# rgb_v2_0.net
KiCad netlist of a schematic drawn in EAGLE
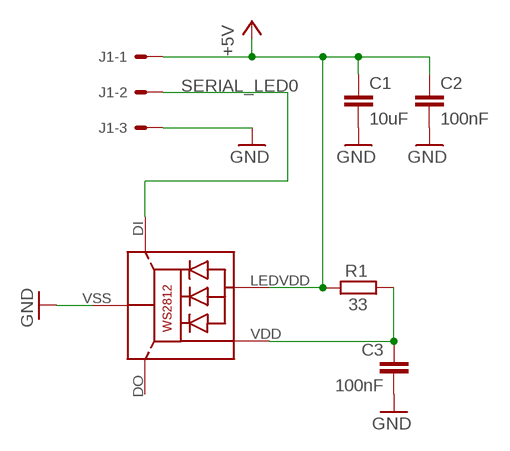
[diagram p0: schematic, sheet 1]

(export (version "E")
  (design (tool "Eeschema 10.0.6"))
  (components
    (comp (ref "C1")
      (value "10uF")
      (footprint "eagle-import:C0603")
      (libsource (lib "eagle-import") (part "C-EUC0603"))
    )
    (comp (ref "C2")
      (value "100nF")
      (footprint "eagle-import:C0402")
      (libsource (lib "eagle-import") (part "C-EUC0402"))
    )
    (comp (ref "C3")
      (value "100nF")
      (footprint "eagle-import:C0402")
      (libsource (lib "eagle-import") (part "C-EUC0402"))
    )
    (comp (ref "J1")
      (value "22-05-7038-03")
      (footprint "eagle-import:7395-03")
      (libsource (lib "eagle-import") (part "22-?-0305-7038"))
    )
    (comp (ref "LED1")
      (value "WS2812LARGER")
      (footprint "eagle-import:WS2812_LARGER")
      (libsource (lib "eagle-import") (part "WS2812LARGER"))
    )
    (comp (ref "R1")
      (value "33")
      (footprint "eagle-import:R0402")
      (libsource (lib "eagle-import") (part "R-EU_R0402"))
    )
  )
  (nets
    (net (code "1") (name "+5V") (class "Default")
      (node (ref "C1") (pin "1") (pinfunction "1_1") (pintype "passive"))
      (node (ref "C2") (pin "1") (pinfunction "1_1") (pintype "passive"))
      (node (ref "J1") (pin "1") (pinfunction "S_1") (pintype "passive"))
      (node (ref "LED1") (pin "LEDVDD") (pinfunction "LEDVDD_LEDVDD") (pintype "power_in"))
      (node (ref "R1") (pin "2") (pinfunction "2_2") (pintype "passive"))
    )
    (net (code "2") (name "/SERIAL_LED0") (class "Default")
      (node (ref "J1") (pin "2") (pinfunction "S_2") (pintype "passive"))
      (node (ref "LED1") (pin "DI") (pinfunction "DI_DI") (pintype "input"))
    )
    (net (code "3") (name "GND") (class "Default")
      (node (ref "C1") (pin "2") (pinfunction "2_2") (pintype "passive"))
      (node (ref "C2") (pin "2") (pinfunction "2_2") (pintype "passive"))
      (node (ref "C3") (pin "2") (pinfunction "2_2") (pintype "passive"))
      (node (ref "J1") (pin "3") (pinfunction "S_3") (pintype "passive"))
      (node (ref "LED1") (pin "VSS") (pinfunction "GND_VSS") (pintype "power_in"))
    )
    (net (code "4") (name "Net-(C3-Pad1)") (class "Default")
      (node (ref "C3") (pin "1") (pinfunction "1_1") (pintype "passive"))
      (node (ref "LED1") (pin "VDD") (pinfunction "VDD_VDD") (pintype "power_in"))
      (node (ref "R1") (pin "1") (pinfunction "1_1") (pintype "passive"))
    )
    (net (code "5") (name "unconnected-(LED1-PadDO)") (class "Default")
      (node (ref "LED1") (pin "DO") (pinfunction "DO_DO") (pintype "output"))
    )
  )
)
